# M-LVDS_PHY.net
KiCad netlist of a schematic drawn in Altium Designer
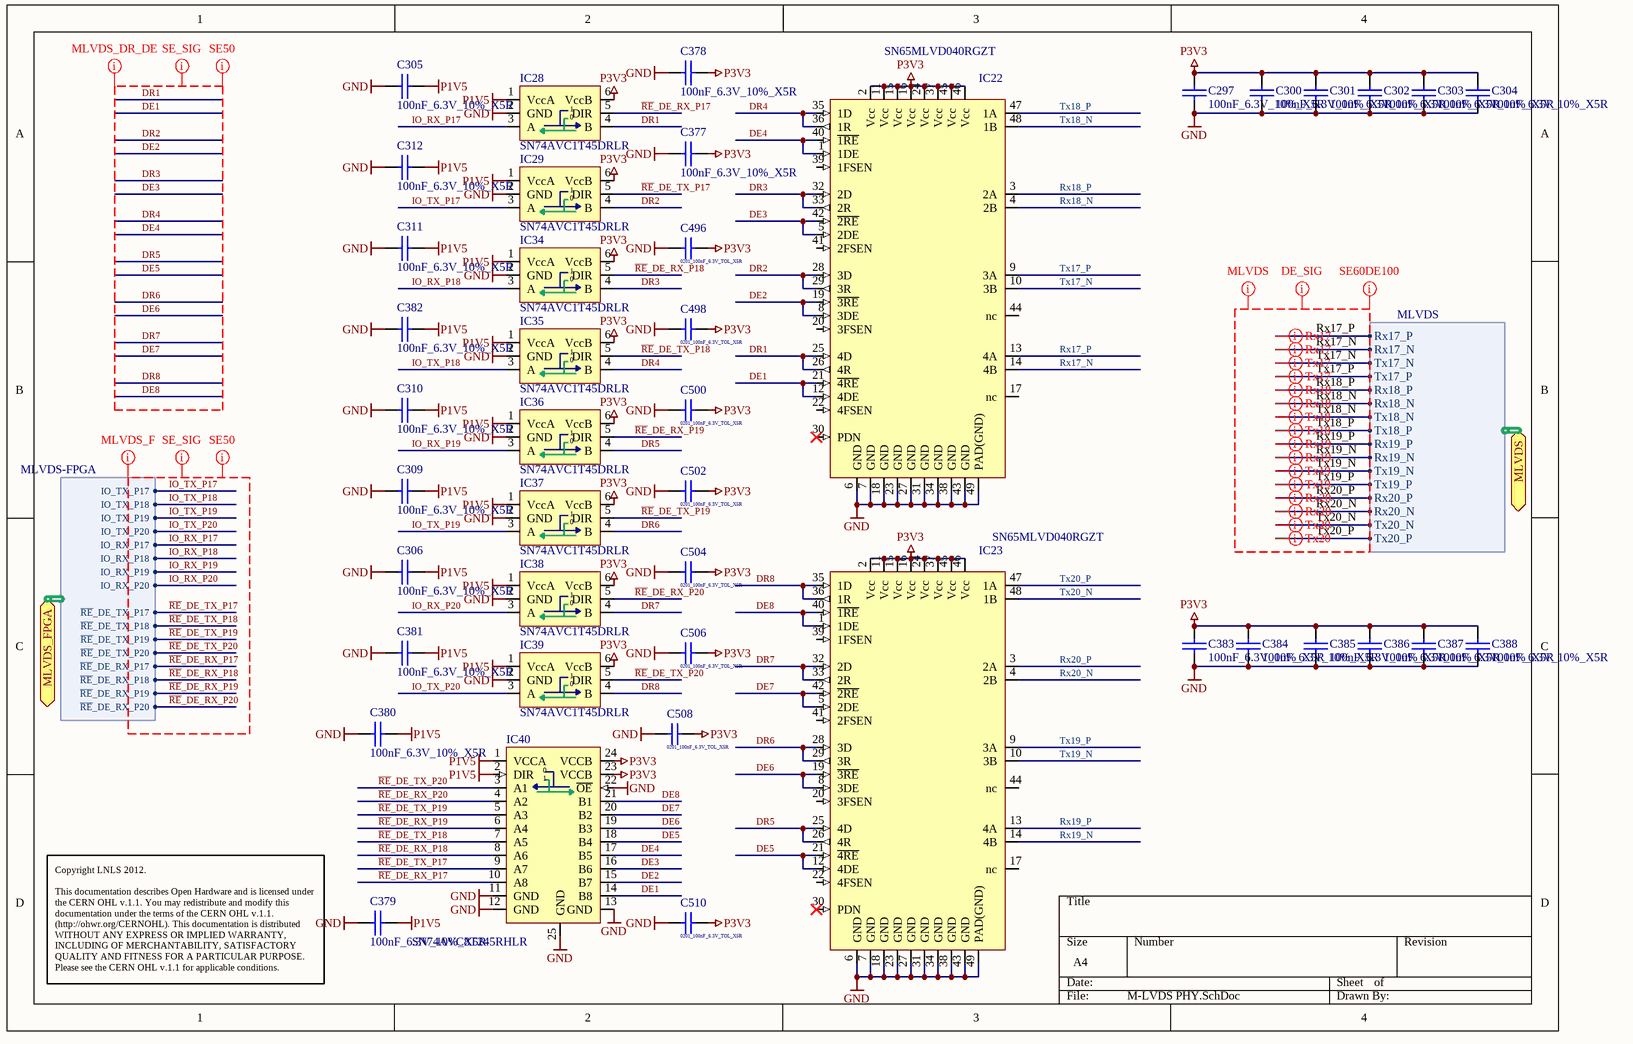
[diagram p0: M-LVDS PHY.SchDoc]

(export (version "E")
  (design (tool "Eeschema 10.0.6"))
  (components
    (comp (ref "C297")
      (value "100nF_6.3V_10%_X5R")
      (footprint "0201C")
      (description "Capacitor SMD")
      (libsource (lib "LIBRARY_SCH") (part "CAP_SMD_0201"))
    )
    (comp (ref "C300")
      (value "100nF_6.3V_10%_X5R")
      (footprint "0201C")
      (description "Capacitor SMD")
      (libsource (lib "LIBRARY_SCH") (part "CAP_SMD_0201"))
    )
    (comp (ref "C301")
      (value "100nF_6.3V_10%_X5R")
      (footprint "0201C")
      (description "Capacitor SMD")
      (libsource (lib "LIBRARY_SCH") (part "CAP_SMD_0201"))
    )
    (comp (ref "C302")
      (value "100nF_6.3V_10%_X5R")
      (footprint "0201C")
      (description "Capacitor SMD")
      (libsource (lib "LIBRARY_SCH") (part "CAP_SMD_0201"))
    )
    (comp (ref "C303")
      (value "100nF_6.3V_10%_X5R")
      (footprint "0201C")
      (description "Capacitor SMD")
      (libsource (lib "LIBRARY_SCH") (part "CAP_SMD_0201"))
    )
    (comp (ref "C304")
      (value "100nF_6.3V_10%_X5R")
      (footprint "0201C")
      (description "Capacitor SMD")
      (libsource (lib "LIBRARY_SCH") (part "CAP_SMD_0201"))
    )
    (comp (ref "C305")
      (value "100nF_6.3V_10%_X5R")
      (footprint "0201C")
      (description "Capacitor SMD")
      (libsource (lib "LIBRARY_SCH") (part "CAP_SMD_0201"))
    )
    (comp (ref "C306")
      (value "100nF_6.3V_10%_X5R")
      (footprint "0201C")
      (description "Capacitor SMD")
      (libsource (lib "LIBRARY_SCH") (part "CAP_SMD_0201"))
    )
    (comp (ref "C309")
      (value "100nF_6.3V_10%_X5R")
      (footprint "0201C")
      (description "Capacitor SMD")
      (libsource (lib "LIBRARY_SCH") (part "CAP_SMD_0201"))
    )
    (comp (ref "C310")
      (value "100nF_6.3V_10%_X5R")
      (footprint "0201C")
      (description "Capacitor SMD")
      (libsource (lib "LIBRARY_SCH") (part "CAP_SMD_0201"))
    )
    (comp (ref "C311")
      (value "100nF_6.3V_10%_X5R")
      (footprint "0201C")
      (description "Capacitor SMD")
      (libsource (lib "LIBRARY_SCH") (part "CAP_SMD_0201"))
    )
    (comp (ref "C312")
      (value "100nF_6.3V_10%_X5R")
      (footprint "0201C")
      (description "Capacitor SMD")
      (libsource (lib "LIBRARY_SCH") (part "CAP_SMD_0201"))
    )
    (comp (ref "C377")
      (value "100nF_6.3V_10%_X5R")
      (footprint "0201C")
      (description "Capacitor SMD")
      (libsource (lib "LIBRARY_SCH") (part "CAP_SMD_0201"))
    )
    (comp (ref "C378")
      (value "100nF_6.3V_10%_X5R")
      (footprint "0201C")
      (description "Capacitor SMD")
      (libsource (lib "LIBRARY_SCH") (part "CAP_SMD_0201"))
    )
    (comp (ref "C379")
      (value "100nF_6.3V_10%_X5R")
      (footprint "0201C")
      (description "Capacitor SMD")
      (libsource (lib "LIBRARY_SCH") (part "CAP_SMD_0201"))
    )
    (comp (ref "C380")
      (value "100nF_6.3V_10%_X5R")
      (footprint "0201C")
      (description "Capacitor SMD")
      (libsource (lib "LIBRARY_SCH") (part "CAP_SMD_0201"))
    )
    (comp (ref "C381")
      (value "100nF_6.3V_10%_X5R")
      (footprint "0201C")
      (description "Capacitor SMD")
      (libsource (lib "LIBRARY_SCH") (part "CAP_SMD_0201"))
    )
    (comp (ref "C382")
      (value "100nF_6.3V_10%_X5R")
      (footprint "0201C")
      (description "Capacitor SMD")
      (libsource (lib "LIBRARY_SCH") (part "CAP_SMD_0201"))
    )
    (comp (ref "C383")
      (value "100nF_6.3V_10%_X5R")
      (footprint "0201C")
      (description "Capacitor SMD")
      (libsource (lib "LIBRARY_SCH") (part "CAP_SMD_0201"))
    )
    (comp (ref "C384")
      (value "100nF_6.3V_10%_X5R")
      (footprint "0201C")
      (description "Capacitor SMD")
      (libsource (lib "LIBRARY_SCH") (part "CAP_SMD_0201"))
    )
    (comp (ref "C385")
      (value "100nF_6.3V_10%_X5R")
      (footprint "0201C")
      (description "Capacitor SMD")
      (libsource (lib "LIBRARY_SCH") (part "CAP_SMD_0201"))
    )
    (comp (ref "C386")
      (value "100nF_6.3V_10%_X5R")
      (footprint "0201C")
      (description "Capacitor SMD")
      (libsource (lib "LIBRARY_SCH") (part "CAP_SMD_0201"))
    )
    (comp (ref "C387")
      (value "100nF_6.3V_10%_X5R")
      (footprint "0201C")
      (description "Capacitor SMD")
      (libsource (lib "LIBRARY_SCH") (part "CAP_SMD_0201"))
    )
    (comp (ref "C388")
      (value "100nF_6.3V_10%_X5R")
      (footprint "0201C")
      (description "Capacitor SMD")
      (libsource (lib "LIBRARY_SCH") (part "CAP_SMD_0201"))
    )
    (comp (ref "C496")
      (value "0201_100nF_6.3V_TOL_X5R")
      (footprint "CAPC0603X33N")
      (fields (field (name "PART NUMBER") "Ceramic_0201"))
      (libsource (lib "Capacitors") (part "Capacitor"))
    )
    (comp (ref "C498")
      (value "0201_100nF_6.3V_TOL_X5R")
      (footprint "CAPC0603X33N")
      (fields (field (name "PART NUMBER") "Ceramic_0201"))
      (libsource (lib "Capacitors") (part "Capacitor"))
    )
    (comp (ref "C500")
      (value "0201_100nF_6.3V_TOL_X5R")
      (footprint "CAPC0603X33N")
      (fields (field (name "PART NUMBER") "Ceramic_0201"))
      (libsource (lib "Capacitors") (part "Capacitor"))
    )
    (comp (ref "C502")
      (value "0201_100nF_6.3V_TOL_X5R")
      (footprint "CAPC0603X33N")
      (fields (field (name "PART NUMBER") "Ceramic_0201"))
      (libsource (lib "Capacitors") (part "Capacitor"))
    )
    (comp (ref "C504")
      (value "0201_100nF_6.3V_TOL_X5R")
      (footprint "CAPC0603X33N")
      (fields (field (name "PART NUMBER") "Ceramic_0201"))
      (libsource (lib "Capacitors") (part "Capacitor"))
    )
    (comp (ref "C506")
      (value "0201_100nF_6.3V_TOL_X5R")
      (footprint "CAPC0603X33N")
      (fields (field (name "PART NUMBER") "Ceramic_0201"))
      (libsource (lib "Capacitors") (part "Capacitor"))
    )
    (comp (ref "C508")
      (value "0201_100nF_6.3V_TOL_X5R")
      (footprint "CAPC0603X33N")
      (fields (field (name "PART NUMBER") "Ceramic_0201"))
      (libsource (lib "Capacitors") (part "Capacitor"))
    )
    (comp (ref "C510")
      (value "0201_100nF_6.3V_TOL_X5R")
      (footprint "CAPC0603X33N")
      (fields (field (name "PART NUMBER") "Ceramic_0201"))
      (libsource (lib "Capacitors") (part "Capacitor"))
    )
    (comp (ref "IC22")
      (value "SN65MLVD040RGZT")
      (footprint "QFN48L")
      (libsource (lib "LIBRARY_SCH") (part "IFC_SN65MLVD040"))
    )
    (comp (ref "IC23")
      (value "SN65MLVD040RGZT")
      (footprint "QFN48L")
      (libsource (lib "LIBRARY_SCH") (part "IFC_SN65MLVD040"))
    )
    (comp (ref "IC28")
      (value "SN74AVC1T45DRLR")
      (footprint "SOT-553")
      (description "1-bit Transceiver Dual Supply (1.4...3.6V)")
      (libsource (lib "LIBRARY_SCH") (part "74AVC1T45"))
    )
    (comp (ref "IC29")
      (value "SN74AVC1T45DRLR")
      (footprint "SOT-553")
      (description "1-bit Transceiver Dual Supply (1.4...3.6V)")
      (libsource (lib "LIBRARY_SCH") (part "74AVC1T45"))
    )
    (comp (ref "IC34")
      (value "SN74AVC1T45DRLR")
      (footprint "SOT-553")
      (description "1-bit Transceiver Dual Supply (1.4...3.6V)")
      (libsource (lib "LIBRARY_SCH") (part "74AVC1T45"))
    )
    (comp (ref "IC35")
      (value "SN74AVC1T45DRLR")
      (footprint "SOT-553")
      (description "1-bit Transceiver Dual Supply (1.4...3.6V)")
      (libsource (lib "LIBRARY_SCH") (part "74AVC1T45"))
    )
    (comp (ref "IC36")
      (value "SN74AVC1T45DRLR")
      (footprint "SOT-553")
      (description "1-bit Transceiver Dual Supply (1.4...3.6V)")
      (libsource (lib "LIBRARY_SCH") (part "74AVC1T45"))
    )
    (comp (ref "IC37")
      (value "SN74AVC1T45DRLR")
      (footprint "SOT-553")
      (description "1-bit Transceiver Dual Supply (1.4...3.6V)")
      (libsource (lib "LIBRARY_SCH") (part "74AVC1T45"))
    )
    (comp (ref "IC38")
      (value "SN74AVC1T45DRLR")
      (footprint "SOT-553")
      (description "1-bit Transceiver Dual Supply (1.4...3.6V)")
      (libsource (lib "LIBRARY_SCH") (part "74AVC1T45"))
    )
    (comp (ref "IC39")
      (value "SN74AVC1T45DRLR")
      (footprint "SOT-553")
      (description "1-bit Transceiver Dual Supply (1.4...3.6V)")
      (libsource (lib "LIBRARY_SCH") (part "74AVC1T45"))
    )
    (comp (ref "IC40")
      (value "SN74AVC8T245RHLR")
      (footprint "QFN50P350X550X100-24N")
      (description "8 channel bidir translator buffer (1.4..3.6V)")
      (libsource (lib "LIBRARY_SCH") (part "74AVC8T245_QFN"))
    )
  )
  (nets
    (net (code "3") (name "/DE1") (class "Default")
      (node (ref "IC22") (pin "12") (pinfunction "4DE_12") (pintype "input"))
      (node (ref "IC22") (pin "21") (pinfunction "~{4RE}_21") (pintype "input"))
      (node (ref "IC40") (pin "14") (pinfunction "B8_14") (pintype "bidirectional"))
    )
    (net (code "4") (name "/DE2") (class "Default")
      (node (ref "IC22") (pin "19") (pinfunction "~{3RE}_19") (pintype "input"))
      (node (ref "IC22") (pin "8") (pinfunction "3DE_8") (pintype "input"))
      (node (ref "IC40") (pin "15") (pinfunction "B7_15") (pintype "bidirectional"))
    )
    (net (code "5") (name "/DE3") (class "Default")
      (node (ref "IC22") (pin "42") (pinfunction "~{2RE}_42") (pintype "input"))
      (node (ref "IC22") (pin "5") (pinfunction "2DE_5") (pintype "input"))
      (node (ref "IC40") (pin "16") (pinfunction "B6_16") (pintype "bidirectional"))
    )
    (net (code "6") (name "/DE4") (class "Default")
      (node (ref "IC22") (pin "1") (pinfunction "1DE_1") (pintype "input"))
      (node (ref "IC22") (pin "40") (pinfunction "~{1RE}_40") (pintype "input"))
      (node (ref "IC40") (pin "17") (pinfunction "B5_17") (pintype "bidirectional"))
    )
    (net (code "7") (name "/DE5") (class "Default")
      (node (ref "IC23") (pin "12") (pinfunction "4DE_12") (pintype "input"))
      (node (ref "IC23") (pin "21") (pinfunction "~{4RE}_21") (pintype "input"))
      (node (ref "IC40") (pin "18") (pinfunction "B4_18") (pintype "bidirectional"))
    )
    (net (code "8") (name "/DE6") (class "Default")
      (node (ref "IC23") (pin "19") (pinfunction "~{3RE}_19") (pintype "input"))
      (node (ref "IC23") (pin "8") (pinfunction "3DE_8") (pintype "input"))
      (node (ref "IC40") (pin "19") (pinfunction "B3_19") (pintype "bidirectional"))
    )
    (net (code "9") (name "/DE7") (class "Default")
      (node (ref "IC23") (pin "42") (pinfunction "~{2RE}_42") (pintype "input"))
      (node (ref "IC23") (pin "5") (pinfunction "2DE_5") (pintype "input"))
      (node (ref "IC40") (pin "20") (pinfunction "B2_20") (pintype "bidirectional"))
    )
    (net (code "10") (name "/DE8") (class "Default")
      (node (ref "IC23") (pin "1") (pinfunction "1DE_1") (pintype "input"))
      (node (ref "IC23") (pin "40") (pinfunction "~{1RE}_40") (pintype "input"))
      (node (ref "IC40") (pin "21") (pinfunction "B1_21") (pintype "bidirectional"))
    )
    (net (code "11") (name "/DR1") (class "Default")
      (node (ref "IC22") (pin "25") (pinfunction "4D_25") (pintype "input"))
      (node (ref "IC22") (pin "26") (pinfunction "4R_26") (pintype "output"))
      (node (ref "IC28") (pin "4") (pinfunction "B_4") (pintype "passive"))
    )
    (net (code "12") (name "/DR2") (class "Default")
      (node (ref "IC22") (pin "28") (pinfunction "3D_28") (pintype "input"))
      (node (ref "IC22") (pin "29") (pinfunction "3R_29") (pintype "output"))
      (node (ref "IC29") (pin "4") (pinfunction "B_4") (pintype "passive"))
    )
    (net (code "13") (name "/DR3") (class "Default")
      (node (ref "IC22") (pin "32") (pinfunction "2D_32") (pintype "input"))
      (node (ref "IC22") (pin "33") (pinfunction "2R_33") (pintype "output"))
      (node (ref "IC34") (pin "4") (pinfunction "B_4") (pintype "passive"))
    )
    (net (code "14") (name "/DR4") (class "Default")
      (node (ref "IC22") (pin "35") (pinfunction "1D_35") (pintype "input"))
      (node (ref "IC22") (pin "36") (pinfunction "1R_36") (pintype "output"))
      (node (ref "IC35") (pin "4") (pinfunction "B_4") (pintype "passive"))
    )
    (net (code "15") (name "/DR5") (class "Default")
      (node (ref "IC23") (pin "25") (pinfunction "4D_25") (pintype "input"))
      (node (ref "IC23") (pin "26") (pinfunction "4R_26") (pintype "output"))
      (node (ref "IC36") (pin "4") (pinfunction "B_4") (pintype "passive"))
    )
    (net (code "16") (name "/DR6") (class "Default")
      (node (ref "IC23") (pin "28") (pinfunction "3D_28") (pintype "input"))
      (node (ref "IC23") (pin "29") (pinfunction "3R_29") (pintype "output"))
      (node (ref "IC37") (pin "4") (pinfunction "B_4") (pintype "passive"))
    )
    (net (code "17") (name "/DR7") (class "Default")
      (node (ref "IC23") (pin "32") (pinfunction "2D_32") (pintype "input"))
      (node (ref "IC23") (pin "33") (pinfunction "2R_33") (pintype "output"))
      (node (ref "IC38") (pin "4") (pinfunction "B_4") (pintype "passive"))
    )
    (net (code "18") (name "/DR8") (class "Default")
      (node (ref "IC23") (pin "35") (pinfunction "1D_35") (pintype "input"))
      (node (ref "IC23") (pin "36") (pinfunction "1R_36") (pintype "output"))
      (node (ref "IC39") (pin "4") (pinfunction "B_4") (pintype "passive"))
    )
    (net (code "19") (name "/IO_RX_P17") (class "Default")
      (node (ref "IC28") (pin "3") (pinfunction "A_3") (pintype "passive"))
    )
    (net (code "20") (name "/IO_RX_P18") (class "Default")
      (node (ref "IC34") (pin "3") (pinfunction "A_3") (pintype "passive"))
    )
    (net (code "21") (name "/IO_RX_P19") (class "Default")
      (node (ref "IC36") (pin "3") (pinfunction "A_3") (pintype "passive"))
    )
    (net (code "22") (name "/IO_RX_P20") (class "Default")
      (node (ref "IC38") (pin "3") (pinfunction "A_3") (pintype "passive"))
    )
    (net (code "23") (name "/IO_TX_P17") (class "Default")
      (node (ref "IC29") (pin "3") (pinfunction "A_3") (pintype "passive"))
    )
    (net (code "24") (name "/IO_TX_P18") (class "Default")
      (node (ref "IC35") (pin "3") (pinfunction "A_3") (pintype "passive"))
    )
    (net (code "25") (name "/IO_TX_P19") (class "Default")
      (node (ref "IC37") (pin "3") (pinfunction "A_3") (pintype "passive"))
    )
    (net (code "26") (name "/IO_TX_P20") (class "Default")
      (node (ref "IC39") (pin "3") (pinfunction "A_3") (pintype "passive"))
    )
    (net (code "27") (name "/Rx17_N") (class "Default")
      (node (ref "IC22") (pin "14") (pinfunction "4B_14") (pintype "bidirectional"))
    )
    (net (code "28") (name "/Rx17_P") (class "Default")
      (node (ref "IC22") (pin "13") (pinfunction "4A_13") (pintype "bidirectional"))
    )
    (net (code "29") (name "/Rx18_N") (class "Default")
      (node (ref "IC22") (pin "4") (pinfunction "2B_4") (pintype "bidirectional"))
    )
    (net (code "30") (name "/Rx18_P") (class "Default")
      (node (ref "IC22") (pin "3") (pinfunction "2A_3") (pintype "bidirectional"))
    )
    (net (code "31") (name "/Rx19_N") (class "Default")
      (node (ref "IC23") (pin "14") (pinfunction "4B_14") (pintype "bidirectional"))
    )
    (net (code "32") (name "/Rx19_P") (class "Default")
      (node (ref "IC23") (pin "13") (pinfunction "4A_13") (pintype "bidirectional"))
    )
    (net (code "33") (name "/Rx20_N") (class "Default")
      (node (ref "IC23") (pin "4") (pinfunction "2B_4") (pintype "bidirectional"))
    )
    (net (code "34") (name "/Rx20_P") (class "Default")
      (node (ref "IC23") (pin "3") (pinfunction "2A_3") (pintype "bidirectional"))
    )
    (net (code "35") (name "/Tx17_N") (class "Default")
      (node (ref "IC22") (pin "10") (pinfunction "3B_10") (pintype "bidirectional"))
    )
    (net (code "36") (name "/Tx17_P") (class "Default")
      (node (ref "IC22") (pin "9") (pinfunction "3A_9") (pintype "bidirectional"))
    )
    (net (code "37") (name "/Tx18_N") (class "Default")
      (node (ref "IC22") (pin "48") (pinfunction "1B_48") (pintype "bidirectional"))
    )
    (net (code "38") (name "/Tx18_P") (class "Default")
      (node (ref "IC22") (pin "47") (pinfunction "1A_47") (pintype "bidirectional"))
    )
    (net (code "39") (name "/Tx19_N") (class "Default")
      (node (ref "IC23") (pin "10") (pinfunction "3B_10") (pintype "bidirectional"))
    )
    (net (code "40") (name "/Tx19_P") (class "Default")
      (node (ref "IC23") (pin "9") (pinfunction "3A_9") (pintype "bidirectional"))
    )
    (net (code "41") (name "/Tx20_N") (class "Default")
      (node (ref "IC23") (pin "48") (pinfunction "1B_48") (pintype "bidirectional"))
    )
    (net (code "42") (name "/Tx20_P") (class "Default")
      (node (ref "IC23") (pin "47") (pinfunction "1A_47") (pintype "bidirectional"))
    )
    (net (code "45") (name "/~{RE}_DE_RX_P17") (class "Default")
      (node (ref "IC28") (pin "5") (pinfunction "DIR_5") (pintype "passive"))
      (node (ref "IC40") (pin "10") (pinfunction "A8_10") (pintype "bidirectional"))
    )
    (net (code "46") (name "/~{RE}_DE_RX_P18") (class "Default")
      (node (ref "IC34") (pin "5") (pinfunction "DIR_5") (pintype "passive"))
      (node (ref "IC40") (pin "8") (pinfunction "A6_8") (pintype "bidirectional"))
    )
    (net (code "47") (name "/~{RE}_DE_RX_P19") (class "Default")
      (node (ref "IC36") (pin "5") (pinfunction "DIR_5") (pintype "passive"))
      (node (ref "IC40") (pin "6") (pinfunction "A4_6") (pintype "bidirectional"))
    )
    (net (code "48") (name "/~{RE}_DE_RX_P20") (class "Default")
      (node (ref "IC38") (pin "5") (pinfunction "DIR_5") (pintype "passive"))
      (node (ref "IC40") (pin "4") (pinfunction "A2_4") (pintype "bidirectional"))
    )
    (net (code "49") (name "/~{RE}_DE_TX_P17") (class "Default")
      (node (ref "IC29") (pin "5") (pinfunction "DIR_5") (pintype "passive"))
      (node (ref "IC40") (pin "9") (pinfunction "A7_9") (pintype "bidirectional"))
    )
    (net (code "50") (name "/~{RE}_DE_TX_P18") (class "Default")
      (node (ref "IC35") (pin "5") (pinfunction "DIR_5") (pintype "passive"))
      (node (ref "IC40") (pin "7") (pinfunction "A5_7") (pintype "bidirectional"))
    )
    (net (code "51") (name "/~{RE}_DE_TX_P19") (class "Default")
      (node (ref "IC37") (pin "5") (pinfunction "DIR_5") (pintype "passive"))
      (node (ref "IC40") (pin "5") (pinfunction "A3_5") (pintype "bidirectional"))
    )
    (net (code "52") (name "/~{RE}_DE_TX_P20") (class "Default")
      (node (ref "IC39") (pin "5") (pinfunction "DIR_5") (pintype "passive"))
      (node (ref "IC40") (pin "3") (pinfunction "A1_3") (pintype "bidirectional"))
    )
    (net (code "53") (name "GND") (class "Default")
      (node (ref "C297") (pin "2") (pinfunction "2_2") (pintype "passive"))
      (node (ref "C300") (pin "2") (pinfunction "2_2") (pintype "passive"))
      (node (ref "C301") (pin "2") (pinfunction "2_2") (pintype "passive"))
      (node (ref "C302") (pin "2") (pinfunction "2_2") (pintype "passive"))
      (node (ref "C303") (pin "2") (pinfunction "2_2") (pintype "passive"))
      (node (ref "C304") (pin "2") (pinfunction "2_2") (pintype "passive"))
      (node (ref "C305") (pin "2") (pinfunction "2_2") (pintype "passive"))
      (node (ref "C306") (pin "1") (pinfunction "1_1") (pintype "passive"))
      (node (ref "C309") (pin "1") (pinfunction "1_1") (pintype "passive"))
      (node (ref "C310") (pin "1") (pinfunction "1_1") (pintype "passive"))
      (node (ref "C311") (pin "1") (pinfunction "1_1") (pintype "passive"))
      (node (ref "C312") (pin "1") (pinfunction "1_1") (pintype "passive"))
      (node (ref "C377") (pin "1") (pinfunction "1_1") (pintype "passive"))
      (node (ref "C378") (pin "1") (pinfunction "1_1") (pintype "passive"))
      (node (ref "C379") (pin "1") (pinfunction "1_1") (pintype "passive"))
      (node (ref "C380") (pin "1") (pinfunction "1_1") (pintype "passive"))
      (node (ref "C381") (pin "1") (pinfunction "1_1") (pintype "passive"))
      (node (ref "C382") (pin "1") (pinfunction "1_1") (pintype "passive"))
      (node (ref "C383") (pin "2") (pinfunction "2_2") (pintype "passive"))
      (node (ref "C384") (pin "2") (pinfunction "2_2") (pintype "passive"))
      (node (ref "C385") (pin "2") (pinfunction "2_2") (pintype "passive"))
      (node (ref "C386") (pin "2") (pinfunction "2_2") (pintype "passive"))
      (node (ref "C387") (pin "2") (pinfunction "2_2") (pintype "passive"))
      (node (ref "C388") (pin "2") (pinfunction "2_2") (pintype "passive"))
      (node (ref "C496") (pin "2") (pinfunction "2_2") (pintype "passive"))
      (node (ref "C498") (pin "2") (pinfunction "2_2") (pintype "passive"))
      (node (ref "C500") (pin "2") (pinfunction "2_2") (pintype "passive"))
      (node (ref "C502") (pin "2") (pinfunction "2_2") (pintype "passive"))
      (node (ref "C504") (pin "2") (pinfunction "2_2") (pintype "passive"))
      (node (ref "C506") (pin "2") (pinfunction "2_2") (pintype "passive"))
      (node (ref "C508") (pin "2") (pinfunction "2_2") (pintype "passive"))
      (node (ref "C510") (pin "2") (pinfunction "2_2") (pintype "passive"))
      (node (ref "IC22") (pin "18") (pinfunction "GND_18") (pintype "power_in"))
      (node (ref "IC22") (pin "23") (pinfunction "GND_23") (pintype "power_in"))
      (node (ref "IC22") (pin "27") (pinfunction "GND_27") (pintype "power_in"))
      (node (ref "IC22") (pin "31") (pinfunction "GND_31") (pintype "power_in"))
      (node (ref "IC22") (pin "34") (pinfunction "GND_34") (pintype "power_in"))
      (node (ref "IC22") (pin "38") (pinfunction "GND_38") (pintype "power_in"))
      (node (ref "IC22") (pin "43") (pinfunction "GND_43") (pintype "power_in"))
      (node (ref "IC22") (pin "49") (pinfunction "PAD(GND)_49") (pintype "power_in"))
      (node (ref "IC22") (pin "6") (pinfunction "GND_6") (pintype "power_in"))
      (node (ref "IC22") (pin "7") (pinfunction "GND_7") (pintype "power_in"))
      (node (ref "IC23") (pin "18") (pinfunction "GND_18") (pintype "power_in"))
      (node (ref "IC23") (pin "23") (pinfunction "GND_23") (pintype "power_in"))
      (node (ref "IC23") (pin "27") (pinfunction "GND_27") (pintype "power_in"))
      (node (ref "IC23") (pin "31") (pinfunction "GND_31") (pintype "power_in"))
      (node (ref "IC23") (pin "34") (pinfunction "GND_34") (pintype "power_in"))
      (node (ref "IC23") (pin "38") (pinfunction "GND_38") (pintype "power_in"))
      (node (ref "IC23") (pin "43") (pinfunction "GND_43") (pintype "power_in"))
      (node (ref "IC23") (pin "49") (pinfunction "PAD(GND)_49") (pintype "power_in"))
      (node (ref "IC23") (pin "6") (pinfunction "GND_6") (pintype "power_in"))
      (node (ref "IC23") (pin "7") (pinfunction "GND_7") (pintype "power_in"))
      (node (ref "IC28") (pin "2") (pinfunction "GND_2") (pintype "passive"))
      (node (ref "IC29") (pin "2") (pinfunction "GND_2") (pintype "passive"))
      (node (ref "IC34") (pin "2") (pinfunction "GND_2") (pintype "passive"))
      (node (ref "IC35") (pin "2") (pinfunction "GND_2") (pintype "passive"))
      (node (ref "IC36") (pin "2") (pinfunction "GND_2") (pintype "passive"))
      (node (ref "IC37") (pin "2") (pinfunction "GND_2") (pintype "passive"))
      (node (ref "IC38") (pin "2") (pinfunction "GND_2") (pintype "passive"))
      (node (ref "IC39") (pin "2") (pinfunction "GND_2") (pintype "passive"))
      (node (ref "IC40") (pin "11") (pinfunction "GND_11") (pintype "power_in"))
      (node (ref "IC40") (pin "12") (pinfunction "GND_12") (pintype "power_in"))
      (node (ref "IC40") (pin "13") (pinfunction "GND_13") (pintype "power_in"))
      (node (ref "IC40") (pin "22") (pinfunction "~{OE}_22") (pintype "input"))
      (node (ref "IC40") (pin "25") (pinfunction "GND_25") (pintype "power_in"))
    )
    (net (code "54") (name "P1V5") (class "Default")
      (node (ref "C305") (pin "1") (pinfunction "1_1") (pintype "passive"))
      (node (ref "C306") (pin "2") (pinfunction "2_2") (pintype "passive"))
      (node (ref "C309") (pin "2") (pinfunction "2_2") (pintype "passive"))
      (node (ref "C310") (pin "2") (pinfunction "2_2") (pintype "passive"))
      (node (ref "C311") (pin "2") (pinfunction "2_2") (pintype "passive"))
      (node (ref "C312") (pin "2") (pinfunction "2_2") (pintype "passive"))
      (node (ref "C379") (pin "2") (pinfunction "2_2") (pintype "passive"))
      (node (ref "C380") (pin "2") (pinfunction "2_2") (pintype "passive"))
      (node (ref "C381") (pin "2") (pinfunction "2_2") (pintype "passive"))
      (node (ref "C382") (pin "2") (pinfunction "2_2") (pintype "passive"))
      (node (ref "IC28") (pin "1") (pinfunction "VccA_1") (pintype "power_in"))
      (node (ref "IC29") (pin "1") (pinfunction "VccA_1") (pintype "power_in"))
      (node (ref "IC34") (pin "1") (pinfunction "VccA_1") (pintype "power_in"))
      (node (ref "IC35") (pin "1") (pinfunction "VccA_1") (pintype "power_in"))
      (node (ref "IC36") (pin "1") (pinfunction "VccA_1") (pintype "power_in"))
      (node (ref "IC37") (pin "1") (pinfunction "VccA_1") (pintype "power_in"))
      (node (ref "IC38") (pin "1") (pinfunction "VccA_1") (pintype "power_in"))
      (node (ref "IC39") (pin "1") (pinfunction "VccA_1") (pintype "power_in"))
      (node (ref "IC40") (pin "1") (pinfunction "VCCA_1") (pintype "power_in"))
      (node (ref "IC40") (pin "2") (pinfunction "DIR_2") (pintype "input"))
    )
    (net (code "55") (name "P3V3") (class "Default")
      (node (ref "C297") (pin "1") (pinfunction "1_1") (pintype "passive"))
      (node (ref "C300") (pin "1") (pinfunction "1_1") (pintype "passive"))
      (node (ref "C301") (pin "1") (pinfunction "1_1") (pintype "passive"))
      (node (ref "C302") (pin "1") (pinfunction "1_1") (pintype "passive"))
      (node (ref "C303") (pin "1") (pinfunction "1_1") (pintype "passive"))
      (node (ref "C304") (pin "1") (pinfunction "1_1") (pintype "passive"))
      (node (ref "C377") (pin "2") (pinfunction "2_2") (pintype "passive"))
      (node (ref "C378") (pin "2") (pinfunction "2_2") (pintype "passive"))
      (node (ref "C383") (pin "1") (pinfunction "1_1") (pintype "passive"))
      (node (ref "C384") (pin "1") (pinfunction "1_1") (pintype "passive"))
      (node (ref "C385") (pin "1") (pinfunction "1_1") (pintype "passive"))
      (node (ref "C386") (pin "1") (pinfunction "1_1") (pintype "passive"))
      (node (ref "C387") (pin "1") (pinfunction "1_1") (pintype "passive"))
      (node (ref "C388") (pin "1") (pinfunction "1_1") (pintype "passive"))
      (node (ref "C496") (pin "1") (pinfunction "1_1") (pintype "passive"))
      (node (ref "C498") (pin "1") (pinfunction "1_1") (pintype "passive"))
      (node (ref "C500") (pin "1") (pinfunction "1_1") (pintype "passive"))
      (node (ref "C502") (pin "1") (pinfunction "1_1") (pintype "passive"))
      (node (ref "C504") (pin "1") (pinfunction "1_1") (pintype "passive"))
      (node (ref "C506") (pin "1") (pinfunction "1_1") (pintype "passive"))
      (node (ref "C508") (pin "1") (pinfunction "1_1") (pintype "passive"))
      (node (ref "C510") (pin "1") (pinfunction "1_1") (pintype "passive"))
      (node (ref "IC22") (pin "11") (pinfunction "Vcc_11") (pintype "power_in"))
      (node (ref "IC22") (pin "15") (pinfunction "Vcc_15") (pintype "power_in"))
      (node (ref "IC22") (pin "16") (pinfunction "Vcc_16") (pintype "power_in"))
      (node (ref "IC22") (pin "2") (pinfunction "Vcc_2") (pintype "power_in"))
      (node (ref "IC22") (pin "24") (pinfunction "Vcc_24") (pintype "power_in"))
      (node (ref "IC22") (pin "37") (pinfunction "Vcc_37") (pintype "power_in"))
      (node (ref "IC22") (pin "45") (pinfunction "Vcc_45") (pintype "power_in"))
      (node (ref "IC22") (pin "46") (pinfunction "Vcc_46") (pintype "power_in"))
      (node (ref "IC23") (pin "11") (pinfunction "Vcc_11") (pintype "power_in"))
      (node (ref "IC23") (pin "15") (pinfunction "Vcc_15") (pintype "power_in"))
      (node (ref "IC23") (pin "16") (pinfunction "Vcc_16") (pintype "power_in"))
      (node (ref "IC23") (pin "2") (pinfunction "Vcc_2") (pintype "power_in"))
      (node (ref "IC23") (pin "24") (pinfunction "Vcc_24") (pintype "power_in"))
      (node (ref "IC23") (pin "37") (pinfunction "Vcc_37") (pintype "power_in"))
      (node (ref "IC23") (pin "45") (pinfunction "Vcc_45") (pintype "power_in"))
      (node (ref "IC23") (pin "46") (pinfunction "Vcc_46") (pintype "power_in"))
      (node (ref "IC28") (pin "6") (pinfunction "VccB_6") (pintype "passive"))
      (node (ref "IC29") (pin "6") (pinfunction "VccB_6") (pintype "passive"))
      (node (ref "IC34") (pin "6") (pinfunction "VccB_6") (pintype "passive"))
      (node (ref "IC35") (pin "6") (pinfunction "VccB_6") (pintype "passive"))
      (node (ref "IC36") (pin "6") (pinfunction "VccB_6") (pintype "passive"))
      (node (ref "IC37") (pin "6") (pinfunction "VccB_6") (pintype "passive"))
      (node (ref "IC38") (pin "6") (pinfunction "VccB_6") (pintype "passive"))
      (node (ref "IC39") (pin "6") (pinfunction "VccB_6") (pintype "passive"))
      (node (ref "IC40") (pin "23") (pinfunction "VCCB_23") (pintype "power_in"))
      (node (ref "IC40") (pin "24") (pinfunction "VCCB_24") (pintype "power_in"))
    )
    (net (code "56") (name "unconnected-(IC22-1FSEN-Pad39)") (class "Default")
      (node (ref "IC22") (pin "39") (pinfunction "1FSEN_39") (pintype "input"))
    )
    (net (code "57") (name "unconnected-(IC22-2FSEN-Pad41)") (class "Default")
      (node (ref "IC22") (pin "41") (pinfunction "2FSEN_41") (pintype "input"))
    )
    (net (code "58") (name "unconnected-(IC22-3FSEN-Pad20)") (class "Default")
      (node (ref "IC22") (pin "20") (pinfunction "3FSEN_20") (pintype "input"))
    )
    (net (code "59") (name "unconnected-(IC22-4FSEN-Pad22)") (class "Default")
      (node (ref "IC22") (pin "22") (pinfunction "4FSEN_22") (pintype "input"))
    )
    (net (code "60") (name "unconnected-(IC22-PDN-Pad30)") (class "Default")
      (node (ref "IC22") (pin "30") (pinfunction "PDN_30") (pintype "input+no_connect"))
    )
    (net (code "61") (name "unconnected-(IC22-nc-Pad17)") (class "Default")
      (node (ref "IC22") (pin "17") (pinfunction "nc_17") (pintype "passive"))
    )
    (net (code "62") (name "unconnected-(IC22-nc-Pad44)") (class "Default")
      (node (ref "IC22") (pin "44") (pinfunction "nc_44") (pintype "power_in"))
    )
    (net (code "63") (name "unconnected-(IC23-1FSEN-Pad39)") (class "Default")
      (node (ref "IC23") (pin "39") (pinfunction "1FSEN_39") (pintype "input"))
    )
    (net (code "64") (name "unconnected-(IC23-2FSEN-Pad41)") (class "Default")
      (node (ref "IC23") (pin "41") (pinfunction "2FSEN_41") (pintype "input"))
    )
    (net (code "65") (name "unconnected-(IC23-3FSEN-Pad20)") (class "Default")
      (node (ref "IC23") (pin "20") (pinfunction "3FSEN_20") (pintype "input"))
    )
    (net (code "66") (name "unconnected-(IC23-4FSEN-Pad22)") (class "Default")
      (node (ref "IC23") (pin "22") (pinfunction "4FSEN_22") (pintype "input"))
    )
    (net (code "67") (name "unconnected-(IC23-PDN-Pad30)") (class "Default")
      (node (ref "IC23") (pin "30") (pinfunction "PDN_30") (pintype "input+no_connect"))
    )
    (net (code "68") (name "unconnected-(IC23-nc-Pad17)") (class "Default")
      (node (ref "IC23") (pin "17") (pinfunction "nc_17") (pintype "passive"))
    )
    (net (code "69") (name "unconnected-(IC23-nc-Pad44)") (class "Default")
      (node (ref "IC23") (pin "44") (pinfunction "nc_44") (pintype "power_in"))
    )
  )
)
